# I2c_Stm8_Uln.net
KiCad netlist of a schematic drawn in EAGLE
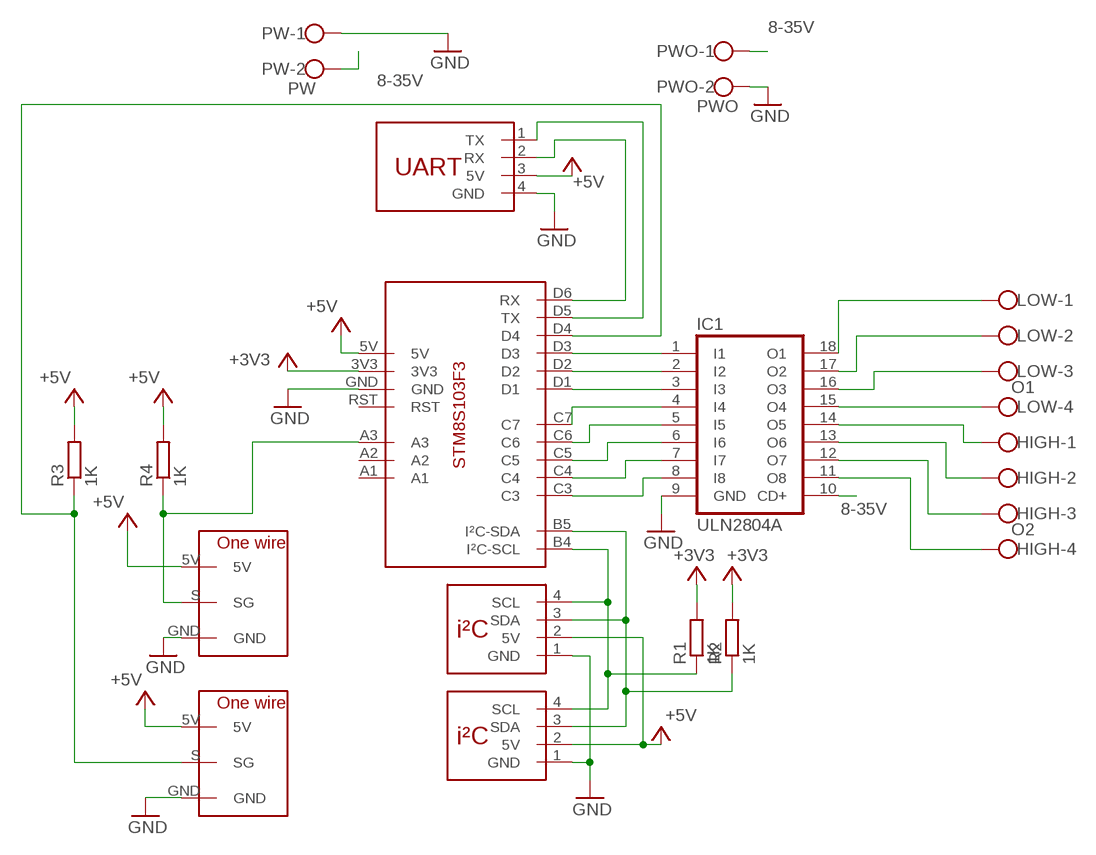
[diagram p0: schematic, sheet 1]

(export (version "E")
  (design (tool "Eeschema 10.0.6"))
  (components
    (comp (ref "HIGH")
      (value "O2")
      (footprint "eagle-import:W237-4")
      (libsource (lib "eagle-import") (part "W237-4"))
    )
    (comp (ref "I2C")
      (value "I2C")
      (footprint "eagle-import:I2C")
      (libsource (lib "eagle-import") (part "I2C"))
    )
    (comp (ref "I2C_SHARE")
      (value "I2C")
      (footprint "eagle-import:I2C")
      (libsource (lib "eagle-import") (part "I2C"))
    )
    (comp (ref "IC1")
      (value "ULN2804A")
      (footprint "eagle-import:DIL18")
      (libsource (lib "eagle-import") (part "ULN2804A"))
    )
    (comp (ref "LOW")
      (value "O1")
      (footprint "eagle-import:W237-4")
      (libsource (lib "eagle-import") (part "W237-4"))
    )
    (comp (ref "PW")
      (value "PW")
      (footprint "eagle-import:W237-102")
      (libsource (lib "eagle-import") (part "W237-102"))
    )
    (comp (ref "PWO")
      (value "PWO")
      (footprint "eagle-import:W237-102")
      (libsource (lib "eagle-import") (part "W237-102"))
    )
    (comp (ref "R1")
      (value "1K")
      (footprint "eagle-import:R1206")
      (libsource (lib "eagle-import") (part "R-EU_R1206"))
    )
    (comp (ref "R2")
      (value "1K")
      (footprint "eagle-import:R1206")
      (libsource (lib "eagle-import") (part "R-EU_R1206"))
    )
    (comp (ref "R3")
      (value "1K")
      (footprint "eagle-import:R1206")
      (libsource (lib "eagle-import") (part "R-EU_R1206"))
    )
    (comp (ref "R4")
      (value "1K")
      (footprint "eagle-import:R1206")
      (libsource (lib "eagle-import") (part "R-EU_R1206"))
    )
    (comp (ref "U$1")
      (value "STM8S103F3-DEVKIT")
      (footprint "eagle-import:STM8S103F3-DEVKIT")
      (libsource (lib "eagle-import") (part "STM8S103F3-DEVKIT"))
    )
    (comp (ref "U$2")
      (value "ONE_WIRE")
      (footprint "eagle-import:ONE_WIRE")
      (libsource (lib "eagle-import") (part "ONE_WIRE"))
    )
    (comp (ref "U$3")
      (value "UARTBIG")
      (footprint "eagle-import:UART")
      (libsource (lib "eagle-import") (part "UARTBIG"))
    )
    (comp (ref "U$4")
      (value "ONE_WIRE")
      (footprint "eagle-import:ONE_WIRE")
      (libsource (lib "eagle-import") (part "ONE_WIRE"))
    )
  )
  (nets
    (net (code "1") (name "+3V3") (class "Default")
      (node (ref "R1") (pin "2") (pinfunction "2_2") (pintype "passive"))
      (node (ref "R2") (pin "2") (pinfunction "2_2") (pintype "passive"))
      (node (ref "U$1") (pin "3V3") (pinfunction "3V3_3V3") (pintype "bidirectional"))
    )
    (net (code "2") (name "+5V") (class "Default")
      (node (ref "I2C") (pin "2") (pinfunction "5V_2") (pintype "bidirectional"))
      (node (ref "I2C_SHARE") (pin "2") (pinfunction "5V_2") (pintype "bidirectional"))
      (node (ref "R3") (pin "2") (pinfunction "2_2") (pintype "passive"))
      (node (ref "R4") (pin "2") (pinfunction "2_2") (pintype "passive"))
      (node (ref "U$1") (pin "5V") (pinfunction "5V_5V") (pintype "bidirectional"))
      (node (ref "U$2") (pin "5V") (pinfunction "5V_5V") (pintype "bidirectional"))
      (node (ref "U$3") (pin "3") (pinfunction "5V_3") (pintype "bidirectional"))
      (node (ref "U$4") (pin "5V") (pinfunction "5V_5V") (pintype "bidirectional"))
    )
    (net (code "3") (name "/8-35V") (class "Default")
      (node (ref "IC1") (pin "10") (pinfunction "CD+_10") (pintype "passive"))
      (node (ref "PW") (pin "2") (pinfunction "KL_2") (pintype "passive"))
      (node (ref "PWO") (pin "1") (pinfunction "KL_1") (pintype "passive"))
    )
    (net (code "4") (name "GND") (class "Default")
      (node (ref "I2C") (pin "1") (pinfunction "GND_1") (pintype "bidirectional"))
      (node (ref "I2C_SHARE") (pin "1") (pinfunction "GND_1") (pintype "bidirectional"))
      (node (ref "IC1") (pin "9") (pinfunction "GND_9") (pintype "power_in"))
      (node (ref "PW") (pin "1") (pinfunction "KL_1") (pintype "passive"))
      (node (ref "PWO") (pin "2") (pinfunction "KL_2") (pintype "passive"))
      (node (ref "U$1") (pin "GND") (pinfunction "GND_GND") (pintype "bidirectional"))
      (node (ref "U$2") (pin "GND") (pinfunction "GND_GND") (pintype "bidirectional"))
      (node (ref "U$3") (pin "4") (pinfunction "GND_4") (pintype "bidirectional"))
      (node (ref "U$4") (pin "GND") (pinfunction "GND_GND") (pintype "bidirectional"))
    )
    (net (code "5") (name "Net-(HIGHA-KL)") (class "Default")
      (node (ref "HIGH") (pin "1") (pinfunction "KL_1") (pintype "passive"))
      (node (ref "IC1") (pin "14") (pinfunction "O5_14") (pintype "open_collector"))
    )
    (net (code "6") (name "Net-(HIGHB-KL)") (class "Default")
      (node (ref "HIGH") (pin "2") (pinfunction "KL_2") (pintype "passive"))
      (node (ref "IC1") (pin "13") (pinfunction "O6_13") (pintype "open_collector"))
    )
    (net (code "7") (name "Net-(HIGHC-KL)") (class "Default")
      (node (ref "HIGH") (pin "3") (pinfunction "KL_3") (pintype "passive"))
      (node (ref "IC1") (pin "12") (pinfunction "O7_12") (pintype "open_collector"))
    )
    (net (code "8") (name "Net-(HIGHD-KL)") (class "Default")
      (node (ref "HIGH") (pin "4") (pinfunction "KL_4") (pintype "passive"))
      (node (ref "IC1") (pin "11") (pinfunction "O8_11") (pintype "open_collector"))
    )
    (net (code "9") (name "Net-(I2C-SCL)") (class "Default")
      (node (ref "I2C") (pin "4") (pinfunction "SCL_4") (pintype "bidirectional"))
      (node (ref "I2C_SHARE") (pin "4") (pinfunction "SCL_4") (pintype "bidirectional"))
      (node (ref "R1") (pin "1") (pinfunction "1_1") (pintype "passive"))
      (node (ref "U$1") (pin "B4") (pinfunction "I²C-SCL_B4") (pintype "bidirectional"))
    )
    (net (code "10") (name "Net-(I2C-SDA)") (class "Default")
      (node (ref "I2C") (pin "3") (pinfunction "SDA_3") (pintype "bidirectional"))
      (node (ref "I2C_SHARE") (pin "3") (pinfunction "SDA_3") (pintype "bidirectional"))
      (node (ref "R2") (pin "1") (pinfunction "1_1") (pintype "passive"))
      (node (ref "U$1") (pin "B5") (pinfunction "I²C-SDA_B5") (pintype "bidirectional"))
    )
    (net (code "11") (name "Net-(IC1-I1)") (class "Default")
      (node (ref "IC1") (pin "1") (pinfunction "I1_1") (pintype "input"))
      (node (ref "U$1") (pin "D3") (pinfunction "D3_D3") (pintype "bidirectional"))
    )
    (net (code "12") (name "Net-(IC1-I2)") (class "Default")
      (node (ref "IC1") (pin "2") (pinfunction "I2_2") (pintype "input"))
      (node (ref "U$1") (pin "D2") (pinfunction "D2_D2") (pintype "bidirectional"))
    )
    (net (code "13") (name "Net-(IC1-I3)") (class "Default")
      (node (ref "IC1") (pin "3") (pinfunction "I3_3") (pintype "input"))
      (node (ref "U$1") (pin "D1") (pinfunction "D1_D1") (pintype "bidirectional"))
    )
    (net (code "14") (name "Net-(IC1-I4)") (class "Default")
      (node (ref "IC1") (pin "4") (pinfunction "I4_4") (pintype "input"))
      (node (ref "U$1") (pin "C7") (pinfunction "C7_C7") (pintype "bidirectional"))
    )
    (net (code "15") (name "Net-(IC1-I5)") (class "Default")
      (node (ref "IC1") (pin "5") (pinfunction "I5_5") (pintype "input"))
      (node (ref "U$1") (pin "C6") (pinfunction "C6_C6") (pintype "bidirectional"))
    )
    (net (code "16") (name "Net-(IC1-I6)") (class "Default")
      (node (ref "IC1") (pin "6") (pinfunction "I6_6") (pintype "input"))
      (node (ref "U$1") (pin "C5") (pinfunction "C5_C5") (pintype "bidirectional"))
    )
    (net (code "17") (name "Net-(IC1-I7)") (class "Default")
      (node (ref "IC1") (pin "7") (pinfunction "I7_7") (pintype "input"))
      (node (ref "U$1") (pin "C4") (pinfunction "C4_C4") (pintype "bidirectional"))
    )
    (net (code "18") (name "Net-(IC1-I8)") (class "Default")
      (node (ref "IC1") (pin "8") (pinfunction "I8_8") (pintype "input"))
      (node (ref "U$1") (pin "C3") (pinfunction "C3_C3") (pintype "bidirectional"))
    )
    (net (code "19") (name "Net-(IC1-O1)") (class "Default")
      (node (ref "IC1") (pin "18") (pinfunction "O1_18") (pintype "open_collector"))
      (node (ref "LOW") (pin "1") (pinfunction "KL_1") (pintype "passive"))
    )
    (net (code "20") (name "Net-(IC1-O2)") (class "Default")
      (node (ref "IC1") (pin "17") (pinfunction "O2_17") (pintype "open_collector"))
      (node (ref "LOW") (pin "2") (pinfunction "KL_2") (pintype "passive"))
    )
    (net (code "21") (name "Net-(IC1-O3)") (class "Default")
      (node (ref "IC1") (pin "16") (pinfunction "O3_16") (pintype "open_collector"))
      (node (ref "LOW") (pin "3") (pinfunction "KL_3") (pintype "passive"))
    )
    (net (code "22") (name "Net-(IC1-O4)") (class "Default")
      (node (ref "IC1") (pin "15") (pinfunction "O4_15") (pintype "open_collector"))
      (node (ref "LOW") (pin "4") (pinfunction "KL_4") (pintype "passive"))
    )
    (net (code "23") (name "Net-(U$1-RX)") (class "Default")
      (node (ref "U$1") (pin "D6") (pinfunction "RX_D6") (pintype "bidirectional"))
      (node (ref "U$3") (pin "2") (pinfunction "RX_2") (pintype "bidirectional"))
    )
    (net (code "24") (name "Net-(U$1-TX)") (class "Default")
      (node (ref "U$1") (pin "D5") (pinfunction "TX_D5") (pintype "bidirectional"))
      (node (ref "U$3") (pin "1") (pinfunction "TX_1") (pintype "bidirectional"))
    )
    (net (code "25") (name "Net-(U$2-SG)") (class "Default")
      (node (ref "R4") (pin "1") (pinfunction "1_1") (pintype "passive"))
      (node (ref "U$1") (pin "A3") (pinfunction "A3_A3") (pintype "bidirectional"))
      (node (ref "U$2") (pin "S") (pinfunction "SG_S") (pintype "bidirectional"))
    )
    (net (code "26") (name "Net-(U$4-SG)") (class "Default")
      (node (ref "R3") (pin "1") (pinfunction "1_1") (pintype "passive"))
      (node (ref "U$1") (pin "D4") (pinfunction "D4_D4") (pintype "bidirectional"))
      (node (ref "U$4") (pin "S") (pinfunction "SG_S") (pintype "bidirectional"))
    )
    (net (code "27") (name "unconnected-(U$1-PadA1)") (class "Default")
      (node (ref "U$1") (pin "A1") (pinfunction "A1_A1") (pintype "bidirectional"))
    )
    (net (code "28") (name "unconnected-(U$1-PadA2)") (class "Default")
      (node (ref "U$1") (pin "A2") (pinfunction "A2_A2") (pintype "bidirectional"))
    )
    (net (code "29") (name "unconnected-(U$1-PadRST)") (class "Default")
      (node (ref "U$1") (pin "RST") (pinfunction "RST_RST") (pintype "bidirectional"))
    )
  )
)
